# SCH_hack-and-roll_2024-03-14.net
KiCad netlist of a schematic drawn in EasyEDA
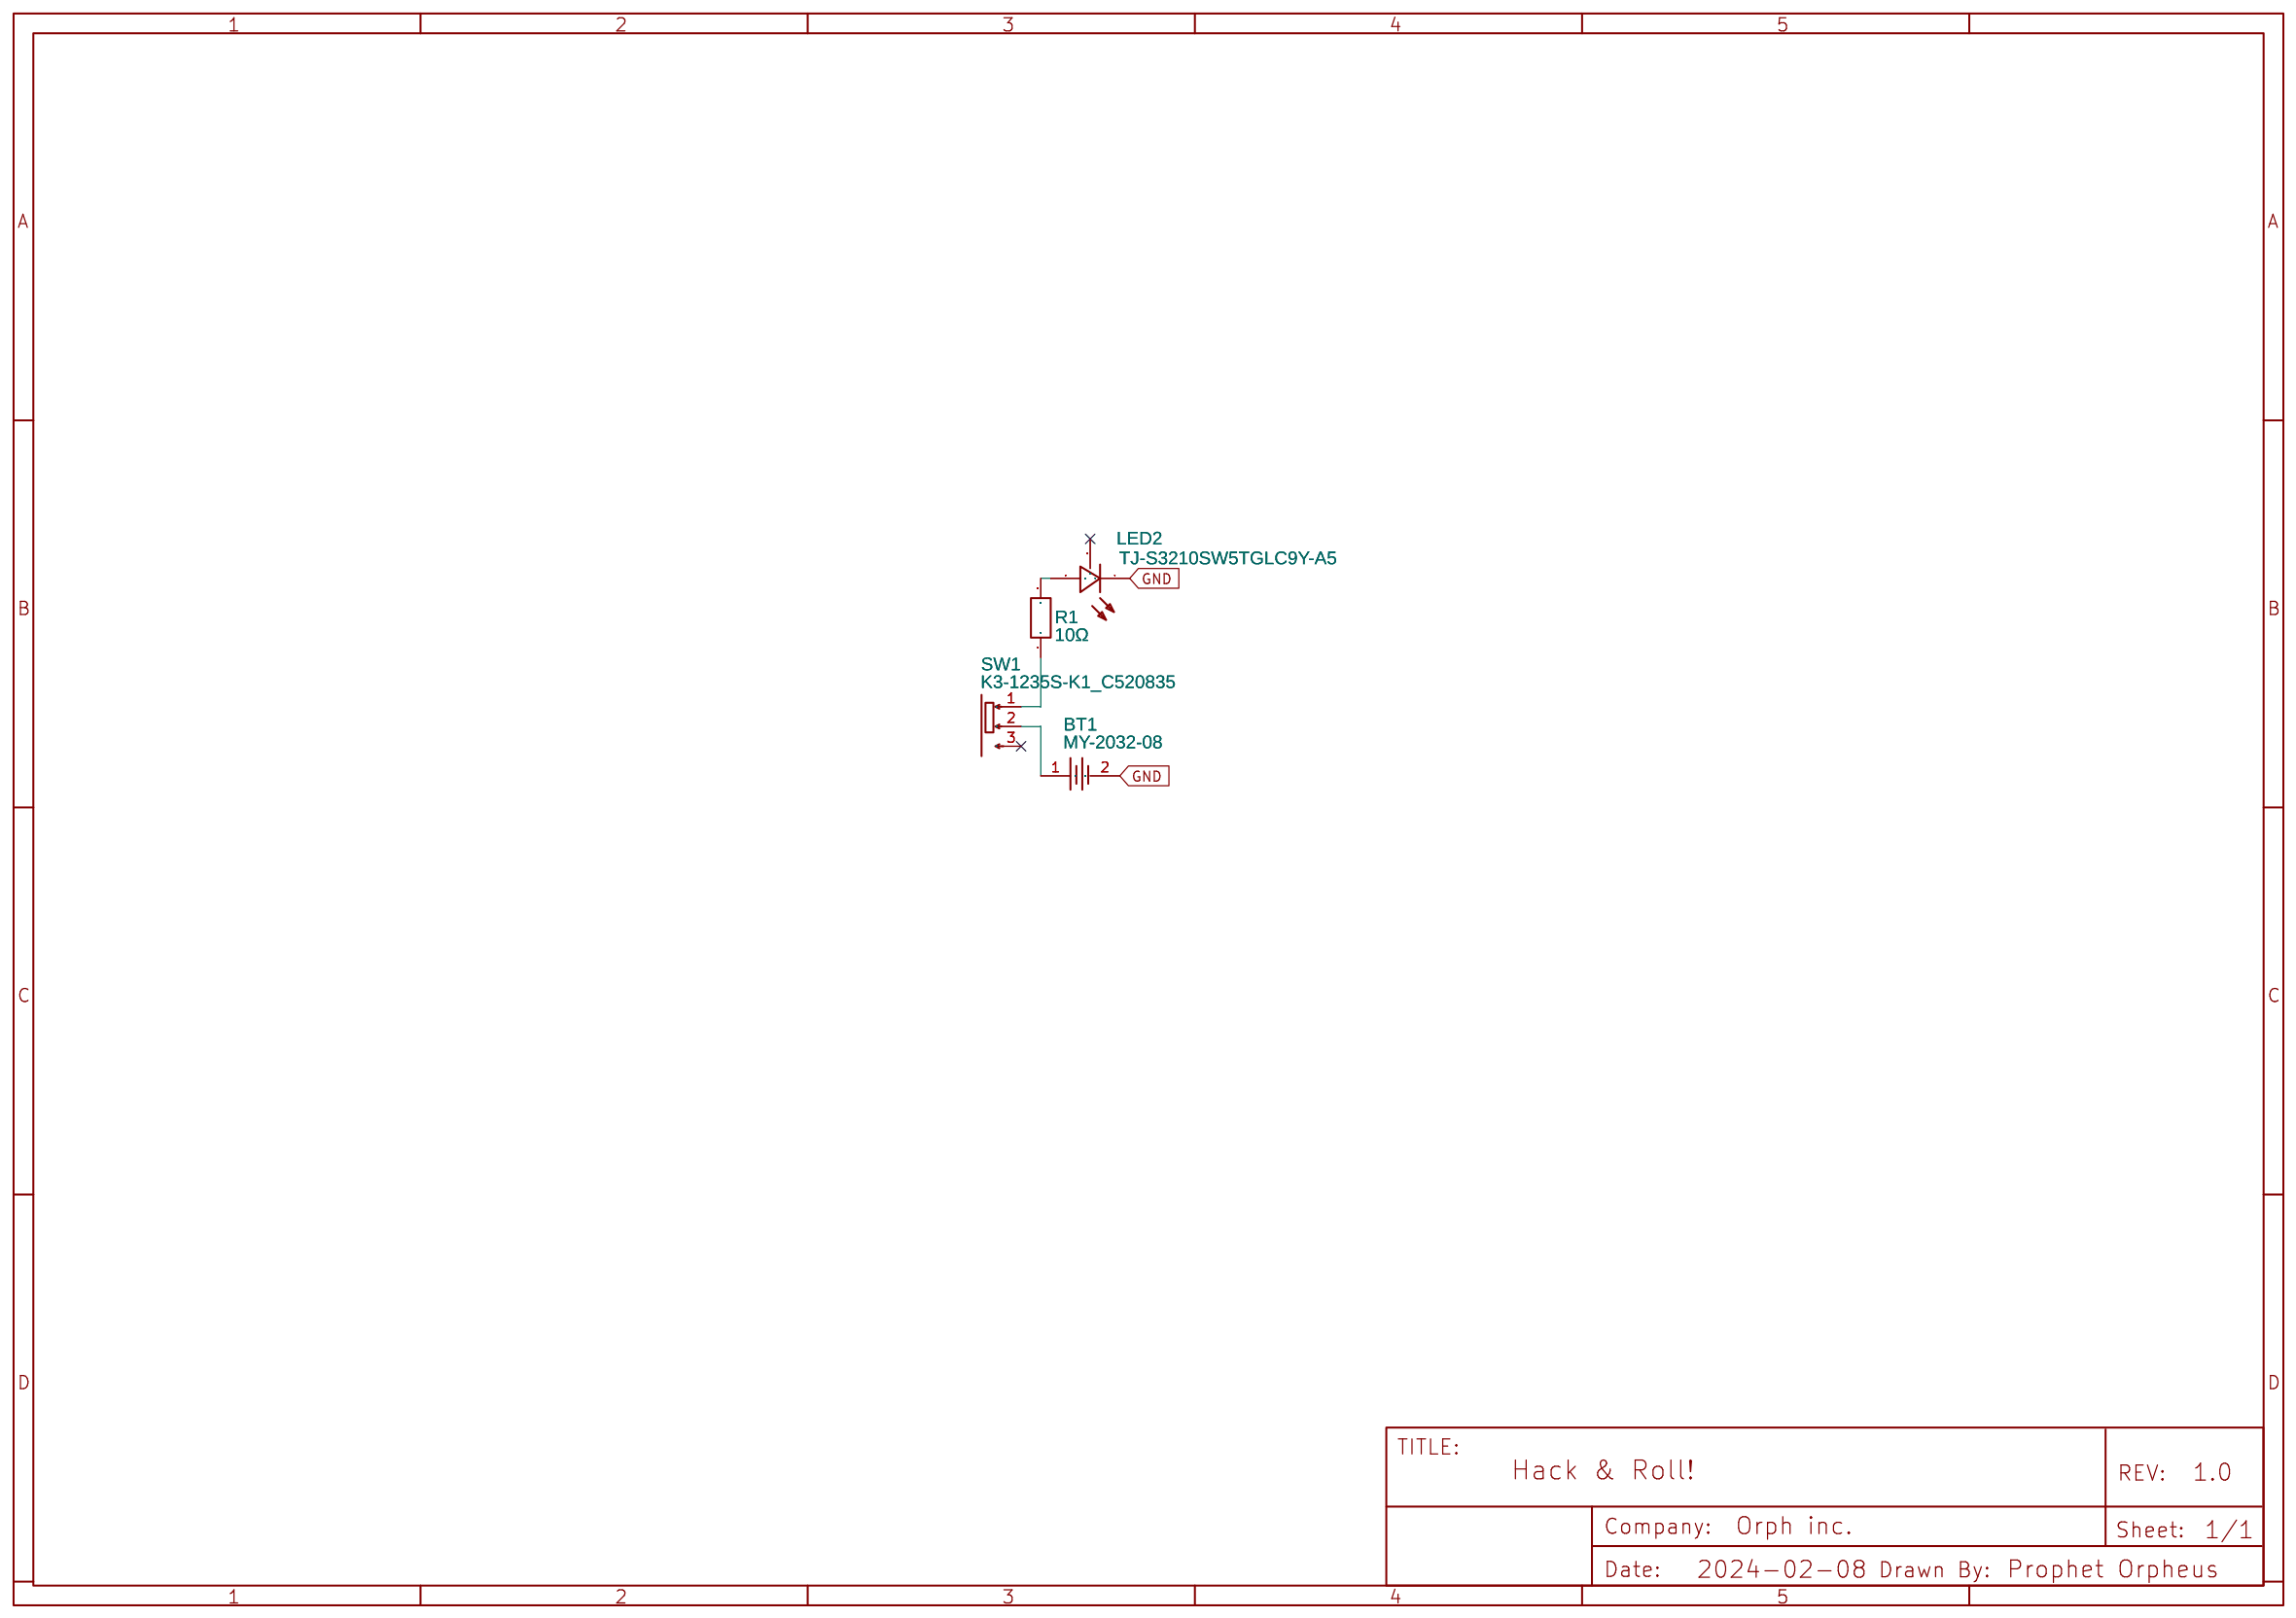
[diagram p0: schematic sheet]

(export (version "E")
  (design (tool "Eeschema 10.0.6"))
  (components
    (comp (ref "BT1")
      (value "MY-2032-08")
      (fields (field (name "Manufacturer") "MYOUNG(美阳)"))
      (libsource (lib "") (part "MY-2032-08"))
    )
    (comp (ref "LED2")
      (value "TJ-S3210SW5TGLC9Y-A5")
      (fields (field (name "Manufacturer") "TOGIALED(统佳)"))
      (libsource (lib "") (part "TJ-S3210SW5TGLC9Y-A5"))
    )
    (comp (ref "R1") (value "10Ω") (libsource (lib "") (part "R_0603_EU")))
    (comp (ref "SW1")
      (value "K3-1235S-K1_C520835")
      (fields (field (name "Manufacturer Part") "K3-1235S-K1") (field (name "Manufacturer") "韩国韩荣"))
      (libsource (lib "") (part "K3-1235S-K1_C520835"))
    )
  )
  (nets
    (net (code "1") (name "GND") (class "Default")
      (node (ref "BT1") (pin "2") (pinfunction "2_2") (pintype "input"))
      (node (ref "LED2") (pin "1") (pinfunction "1_1") (pintype "unspecified"))
    )
    (net (code "2") (name "Net-(BT1-Pad1)") (class "Default")
      (node (ref "BT1") (pin "1") (pinfunction "1_1") (pintype "input"))
      (node (ref "SW1") (pin "2") (pinfunction "2_2") (pintype "unspecified"))
    )
    (net (code "3") (name "Net-(LED2-Pad2)") (class "Default")
      (node (ref "LED2") (pin "2") (pinfunction "2_2") (pintype "unspecified"))
      (node (ref "R1") (pin "2") (pinfunction "2_2") (pintype "unspecified"))
    )
    (net (code "4") (name "Net-(R1-Pad1)") (class "Default")
      (node (ref "R1") (pin "1") (pinfunction "1_1") (pintype "unspecified"))
      (node (ref "SW1") (pin "1") (pinfunction "1_1") (pintype "unspecified"))
    )
    (net (code "5") (name "unconnected-(LED2-Pad3)") (class "Default")
      (node (ref "LED2") (pin "3") (pinfunction "3_3") (pintype "unspecified+no_connect"))
    )
    (net (code "6") (name "unconnected-(SW1-Pad3)") (class "Default")
      (node (ref "SW1") (pin "3") (pinfunction "3_3") (pintype "unspecified+no_connect"))
    )
  )
)
